# 3V3_voltage_regulato.net
KiCad netlist of a schematic drawn in Altium Designer
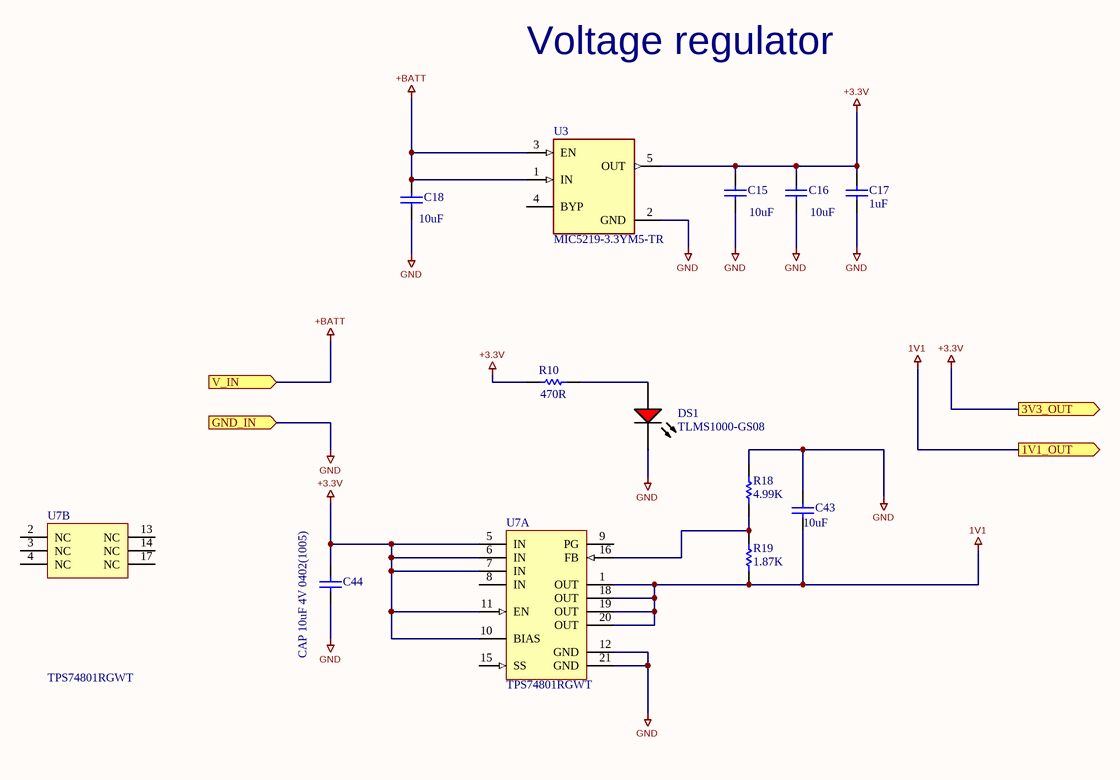
[diagram p0: 3V3 voltage regulato.SchDoc]

(export (version "E")
  (design (tool "Eeschema 10.0.6"))
  (components
    (comp (ref "C15")
      (value "10uF")
      (footprint "CAPC1608X90X35NL10T15")
      (fields (field (name "PART NUMBER") "GRM188R60J106ME47D") (field (name "MANUFACTURER") "Murata"))
      (libsource (lib "Altium Content Vault") (part "CAP"))
    )
    (comp (ref "C16")
      (value "10uF")
      (footprint "CAPC1608X90X35NL10T15")
      (fields (field (name "PART NUMBER") "GRM188R60J106ME47D") (field (name "MANUFACTURER") "Murata"))
      (libsource (lib "Altium Content Vault") (part "CAP"))
    )
    (comp (ref "C17")
      (value "1uF")
      (footprint "CAPC1608X90X35LL10T15")
      (fields (field (name "MANUFACTURER") "Murata") (field (name "PART NUMBER") "GRM188R61E105KA12D"))
      (libsource (lib "Altium Content Vault") (part "CAP"))
    )
    (comp (ref "C18")
      (value "10uF")
      (footprint "CAPC1608X90X35NL10T15")
      (fields (field (name "PART NUMBER") "GRM188R60J106ME47D") (field (name "MANUFACTURER") "Murata"))
      (libsource (lib "Altium Content Vault") (part "CAP"))
    )
    (comp (ref "C43")
      (value "10uF")
      (footprint "CAPC0402(1005)60_L")
      (description "CAP 10uF 4V ±20% 0402 (1005 Metric) Thickness 0.6mm SMD")
      (fields (field (name "TOLERANCE") "Â±20%"))
      (libsource (lib "Altium Content Vault") (part "CAP"))
    )
    (comp (ref "C44")
      (value "CAP 10uF 4V 0402(1005)")
      (footprint "CAPC0402(1005)60_L")
      (description "CAP 10uF 4V ±20% 0402 (1005 Metric) Thickness 0.6mm SMD")
      (fields (field (name "TOLERANCE") "Â±20%"))
      (libsource (lib "Altium Content Vault") (part "CAP"))
    )
    (comp (ref "DS1")
      (value "TLMS1000-GS08")
      (footprint "VISH-TLMS1000_V")
      (description "Low Current LED, 40 mW, 1.8 V, -40 to 100 degC, 2-Pin SMD (0603), RoHS, Tape and Reel")
      (fields (field (name "MANUFACTURER") "Vishay"))
      (libsource (lib "Altium Content Vault") (part "LED-RED-AK-2"))
    )
    (comp (ref "R10")
      (value "470R")
      (footprint "RESC1608X55X25LL10T15")
      (libsource (lib "Altium Content Vault") (part "RES-2"))
    )
    (comp (ref "R18")
      (value "4.99K")
      (footprint "RESC0402(1005)_N")
      (description "Jumper 0402 (1005 Metric)")
      (fields (field (name "TOLERANCE") "None"))
      (libsource (lib "Altium Content Vault") (part "RES"))
    )
    (comp (ref "R19")
      (value "1.87K")
      (footprint "RESC0402(1005)_N")
      (description "Jumper 0402 (1005 Metric)")
      (fields (field (name "TOLERANCE") "None"))
      (libsource (lib "Altium Content Vault") (part "RES"))
    )
    (comp (ref "U3")
      (value "MIC5219-3.3YM5-TR")
      (footprint "FP-SOT23-5LD-PL-1-IPC_C")
      (description "IC REG LINEAR 3.3V 500MA SOT23-5")
      (libsource (lib "Altium Content Vault") (part "16b36b16d6b7b40c29ab14718bc3058"))
    )
    (comp (ref "U7")
      (value "TPS74801RGWT")
      (footprint "RGW0020A_V")
      (fields (field (name "MANUFACTURER") "Texas Instruments"))
      (libsource (lib "Altium Content Vault") (part "TI-TPS74801RGW20-3150X3150TP"))
    )
  )
  (nets
    (net (code "1") (name "+3.3V") (class "Default")
      (node (ref "C15") (pin "2") (pinfunction "2_2") (pintype "passive"))
      (node (ref "C16") (pin "2") (pinfunction "2_2") (pintype "passive"))
      (node (ref "C17") (pin "2") (pinfunction "2_2") (pintype "passive"))
      (node (ref "C44") (pin "2") (pinfunction "2_2") (pintype "passive"))
      (node (ref "R10") (pin "1") (pinfunction "1_1") (pintype "passive"))
      (node (ref "U3") (pin "5") (pinfunction "OUT_5") (pintype "output"))
      (node (ref "U7") (pin "10") (pinfunction "BIAS_10") (pintype "power_in"))
      (node (ref "U7") (pin "11") (pinfunction "EN_11") (pintype "input"))
      (node (ref "U7") (pin "5") (pinfunction "IN_5") (pintype "power_in"))
      (node (ref "U7") (pin "6") (pinfunction "IN_6") (pintype "power_in"))
      (node (ref "U7") (pin "7") (pinfunction "IN_7") (pintype "power_in"))
    )
    (net (code "2") (name "+BATT") (class "Default")
      (node (ref "C18") (pin "2") (pinfunction "2_2") (pintype "passive"))
      (node (ref "U3") (pin "1") (pinfunction "IN_1") (pintype "input"))
      (node (ref "U3") (pin "3") (pinfunction "EN_3") (pintype "input"))
    )
    (net (code "3") (name "1V1") (class "Default")
      (node (ref "C43") (pin "1") (pinfunction "1_1") (pintype "passive"))
      (node (ref "R19") (pin "1") (pinfunction "1_1") (pintype "passive"))
      (node (ref "U7") (pin "1") (pinfunction "OUT_1") (pintype "power_in"))
      (node (ref "U7") (pin "18") (pinfunction "OUT_18") (pintype "power_in"))
      (node (ref "U7") (pin "19") (pinfunction "OUT_19") (pintype "power_in"))
      (node (ref "U7") (pin "20") (pinfunction "OUT_20") (pintype "power_in"))
    )
    (net (code "4") (name "GND") (class "Default")
      (node (ref "C15") (pin "1") (pinfunction "1_1") (pintype "passive"))
      (node (ref "C16") (pin "1") (pinfunction "1_1") (pintype "passive"))
      (node (ref "C17") (pin "1") (pinfunction "1_1") (pintype "passive"))
      (node (ref "C18") (pin "1") (pinfunction "1_1") (pintype "passive"))
      (node (ref "C43") (pin "2") (pinfunction "2_2") (pintype "passive"))
      (node (ref "C44") (pin "1") (pinfunction "1_1") (pintype "passive"))
      (node (ref "DS1") (pin "2") (pinfunction "K_2") (pintype "passive"))
      (node (ref "R18") (pin "2") (pinfunction "2_2") (pintype "passive"))
      (node (ref "U3") (pin "2") (pinfunction "GND_2") (pintype "power_in"))
      (node (ref "U7") (pin "12") (pinfunction "GND_12") (pintype "power_in"))
      (node (ref "U7") (pin "21") (pinfunction "GND_21") (pintype "power_in"))
    )
    (net (code "5") (name "Net-(DS1-A)") (class "Default")
      (node (ref "DS1") (pin "1") (pinfunction "A_1") (pintype "passive"))
      (node (ref "R10") (pin "2") (pinfunction "2_2") (pintype "passive"))
    )
    (net (code "6") (name "Net-(U7A-FB)") (class "Default")
      (node (ref "R18") (pin "1") (pinfunction "1_1") (pintype "passive"))
      (node (ref "R19") (pin "2") (pinfunction "2_2") (pintype "passive"))
      (node (ref "U7") (pin "16") (pinfunction "FB_16") (pintype "input"))
    )
    (net (code "7") (name "unconnected-(U3-BYP-Pad4)") (class "Default")
      (node (ref "U3") (pin "4") (pinfunction "BYP_4") (pintype "passive"))
    )
    (net (code "8") (name "unconnected-(U7A-IN-Pad8)") (class "Default")
      (node (ref "U7") (pin "8") (pinfunction "IN_8") (pintype "power_in"))
    )
    (net (code "9") (name "unconnected-(U7A-PG-Pad9)") (class "Default")
      (node (ref "U7") (pin "9") (pinfunction "PG_9") (pintype "tri_state"))
    )
    (net (code "10") (name "unconnected-(U7A-SS-Pad15)") (class "Default")
      (node (ref "U7") (pin "15") (pinfunction "SS_15") (pintype "input"))
    )
    (net (code "11") (name "unconnected-(U7B-NC-Pad2)") (class "Default")
      (node (ref "U7") (pin "2") (pinfunction "NC_2") (pintype "passive"))
    )
    (net (code "12") (name "unconnected-(U7B-NC-Pad3)") (class "Default")
      (node (ref "U7") (pin "3") (pinfunction "NC_3") (pintype "passive"))
    )
    (net (code "13") (name "unconnected-(U7B-NC-Pad4)") (class "Default")
      (node (ref "U7") (pin "4") (pinfunction "NC_4") (pintype "passive"))
    )
    (net (code "14") (name "unconnected-(U7B-NC-Pad13)") (class "Default")
      (node (ref "U7") (pin "13") (pinfunction "NC_13") (pintype "passive"))
    )
    (net (code "15") (name "unconnected-(U7B-NC-Pad14)") (class "Default")
      (node (ref "U7") (pin "14") (pinfunction "NC_14") (pintype "passive"))
    )
    (net (code "16") (name "unconnected-(U7B-NC-Pad17)") (class "Default")
      (node (ref "U7") (pin "17") (pinfunction "NC_17") (pintype "passive"))
    )
  )
)
